# Memory_Address_Decoder.net
KiCad netlist of a schematic drawn in Altium Designer
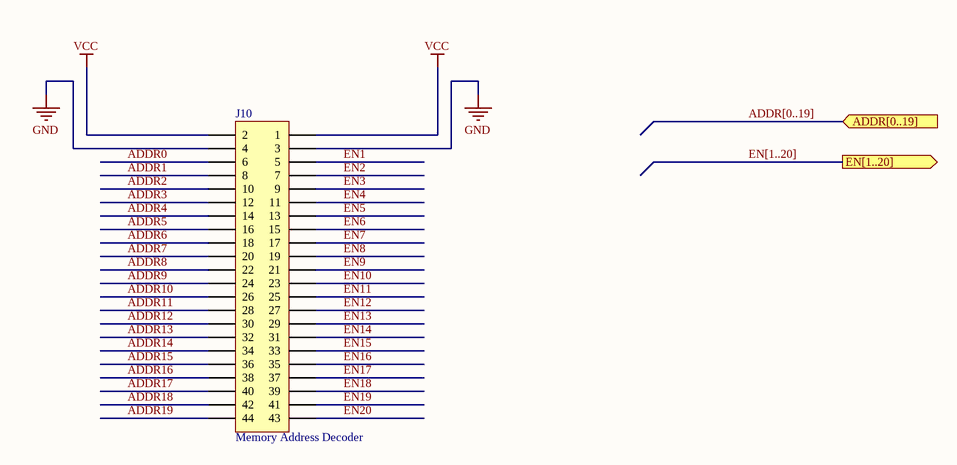
[diagram p0: Memory Address Decoder.SchDoc]

(export (version "E")
  (design (tool "Eeschema 10.0.6"))
  (components
    (comp (ref "J10")
      (value "Memory Address Decoder")
      (footprint "HDR2X22")
      (description "Header, 22-Pin, Dual row")
      (fields (field (name "PUBLISHER") "Altium Limited"))
      (libsource (lib "Miscellaneous Connectors") (part "Header 22X2"))
    )
  )
  (nets
    (net (code "1") (name "/ADDR0") (class "Default")
      (node (ref "J10") (pin "6") (pinfunction "6_6") (pintype "passive"))
    )
    (net (code "2") (name "/ADDR1") (class "Default")
      (node (ref "J10") (pin "8") (pinfunction "8_8") (pintype "passive"))
    )
    (net (code "3") (name "/ADDR2") (class "Default")
      (node (ref "J10") (pin "10") (pinfunction "10_10") (pintype "passive"))
    )
    (net (code "4") (name "/ADDR3") (class "Default")
      (node (ref "J10") (pin "12") (pinfunction "12_12") (pintype "passive"))
    )
    (net (code "5") (name "/ADDR4") (class "Default")
      (node (ref "J10") (pin "14") (pinfunction "14_14") (pintype "passive"))
    )
    (net (code "6") (name "/ADDR5") (class "Default")
      (node (ref "J10") (pin "16") (pinfunction "16_16") (pintype "passive"))
    )
    (net (code "7") (name "/ADDR6") (class "Default")
      (node (ref "J10") (pin "18") (pinfunction "18_18") (pintype "passive"))
    )
    (net (code "8") (name "/ADDR7") (class "Default")
      (node (ref "J10") (pin "20") (pinfunction "20_20") (pintype "passive"))
    )
    (net (code "9") (name "/ADDR8") (class "Default")
      (node (ref "J10") (pin "22") (pinfunction "22_22") (pintype "passive"))
    )
    (net (code "10") (name "/ADDR9") (class "Default")
      (node (ref "J10") (pin "24") (pinfunction "24_24") (pintype "passive"))
    )
    (net (code "11") (name "/ADDR10") (class "Default")
      (node (ref "J10") (pin "26") (pinfunction "26_26") (pintype "passive"))
    )
    (net (code "12") (name "/ADDR11") (class "Default")
      (node (ref "J10") (pin "28") (pinfunction "28_28") (pintype "passive"))
    )
    (net (code "13") (name "/ADDR12") (class "Default")
      (node (ref "J10") (pin "30") (pinfunction "30_30") (pintype "passive"))
    )
    (net (code "14") (name "/ADDR13") (class "Default")
      (node (ref "J10") (pin "32") (pinfunction "32_32") (pintype "passive"))
    )
    (net (code "15") (name "/ADDR14") (class "Default")
      (node (ref "J10") (pin "34") (pinfunction "34_34") (pintype "passive"))
    )
    (net (code "16") (name "/ADDR15") (class "Default")
      (node (ref "J10") (pin "36") (pinfunction "36_36") (pintype "passive"))
    )
    (net (code "17") (name "/ADDR16") (class "Default")
      (node (ref "J10") (pin "38") (pinfunction "38_38") (pintype "passive"))
    )
    (net (code "18") (name "/ADDR17") (class "Default")
      (node (ref "J10") (pin "40") (pinfunction "40_40") (pintype "passive"))
    )
    (net (code "19") (name "/ADDR18") (class "Default")
      (node (ref "J10") (pin "42") (pinfunction "42_42") (pintype "passive"))
    )
    (net (code "20") (name "/ADDR19") (class "Default")
      (node (ref "J10") (pin "44") (pinfunction "44_44") (pintype "passive"))
    )
    (net (code "22") (name "/EN1") (class "Default")
      (node (ref "J10") (pin "5") (pinfunction "5_5") (pintype "passive"))
    )
    (net (code "23") (name "/EN2") (class "Default")
      (node (ref "J10") (pin "7") (pinfunction "7_7") (pintype "passive"))
    )
    (net (code "24") (name "/EN3") (class "Default")
      (node (ref "J10") (pin "9") (pinfunction "9_9") (pintype "passive"))
    )
    (net (code "25") (name "/EN4") (class "Default")
      (node (ref "J10") (pin "11") (pinfunction "11_11") (pintype "passive"))
    )
    (net (code "26") (name "/EN5") (class "Default")
      (node (ref "J10") (pin "13") (pinfunction "13_13") (pintype "passive"))
    )
    (net (code "27") (name "/EN6") (class "Default")
      (node (ref "J10") (pin "15") (pinfunction "15_15") (pintype "passive"))
    )
    (net (code "28") (name "/EN7") (class "Default")
      (node (ref "J10") (pin "17") (pinfunction "17_17") (pintype "passive"))
    )
    (net (code "29") (name "/EN8") (class "Default")
      (node (ref "J10") (pin "19") (pinfunction "19_19") (pintype "passive"))
    )
    (net (code "30") (name "/EN9") (class "Default")
      (node (ref "J10") (pin "21") (pinfunction "21_21") (pintype "passive"))
    )
    (net (code "31") (name "/EN10") (class "Default")
      (node (ref "J10") (pin "23") (pinfunction "23_23") (pintype "passive"))
    )
    (net (code "32") (name "/EN11") (class "Default")
      (node (ref "J10") (pin "25") (pinfunction "25_25") (pintype "passive"))
    )
    (net (code "33") (name "/EN12") (class "Default")
      (node (ref "J10") (pin "27") (pinfunction "27_27") (pintype "passive"))
    )
    (net (code "34") (name "/EN13") (class "Default")
      (node (ref "J10") (pin "29") (pinfunction "29_29") (pintype "passive"))
    )
    (net (code "35") (name "/EN14") (class "Default")
      (node (ref "J10") (pin "31") (pinfunction "31_31") (pintype "passive"))
    )
    (net (code "36") (name "/EN15") (class "Default")
      (node (ref "J10") (pin "33") (pinfunction "33_33") (pintype "passive"))
    )
    (net (code "37") (name "/EN16") (class "Default")
      (node (ref "J10") (pin "35") (pinfunction "35_35") (pintype "passive"))
    )
    (net (code "38") (name "/EN17") (class "Default")
      (node (ref "J10") (pin "37") (pinfunction "37_37") (pintype "passive"))
    )
    (net (code "39") (name "/EN18") (class "Default")
      (node (ref "J10") (pin "39") (pinfunction "39_39") (pintype "passive"))
    )
    (net (code "40") (name "/EN19") (class "Default")
      (node (ref "J10") (pin "41") (pinfunction "41_41") (pintype "passive"))
    )
    (net (code "41") (name "/EN20") (class "Default")
      (node (ref "J10") (pin "43") (pinfunction "43_43") (pintype "passive"))
    )
    (net (code "43") (name "GND") (class "Default")
      (node (ref "J10") (pin "3") (pinfunction "3_3") (pintype "passive"))
      (node (ref "J10") (pin "4") (pinfunction "4_4") (pintype "passive"))
    )
    (net (code "44") (name "VCC") (class "Default")
      (node (ref "J10") (pin "1") (pinfunction "1_1") (pintype "passive"))
      (node (ref "J10") (pin "2") (pinfunction "2_2") (pintype "passive"))
    )
  )
)
